# V4.net
KiCad netlist of a schematic drawn in Altium Designer
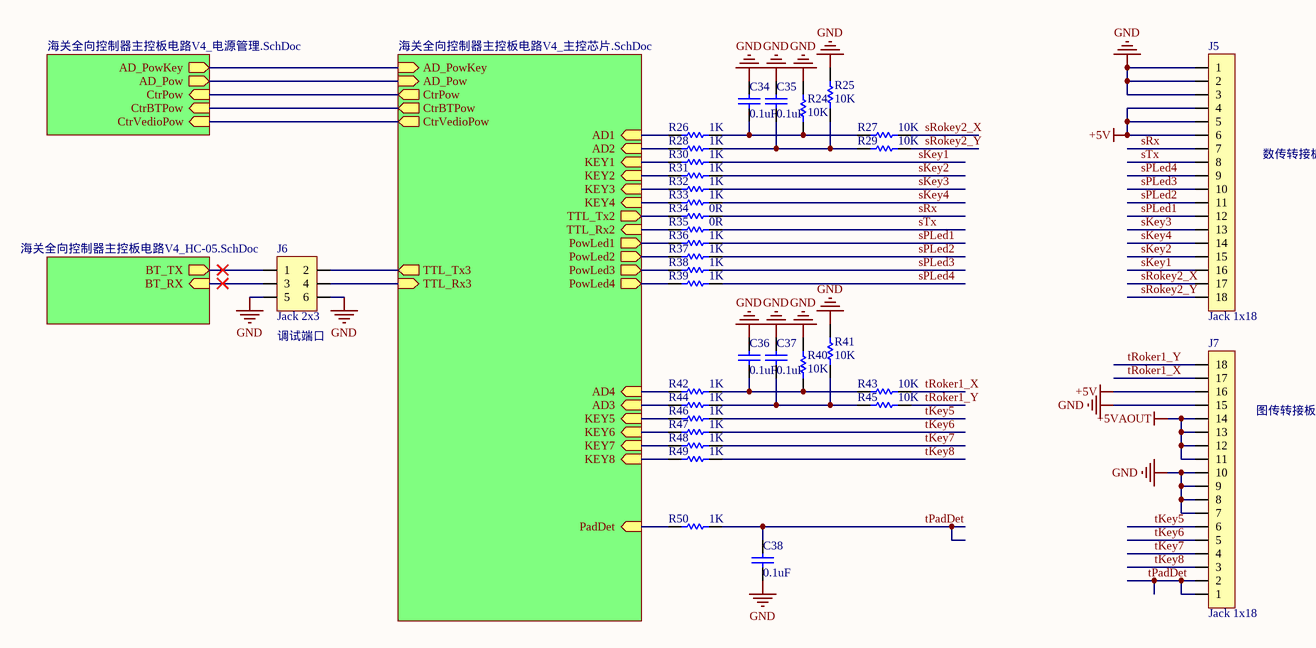
[diagram p0: 海关全向控制器主控板电路V4_系统管理.SchDoc]

(export (version "E")
  (design (tool "Eeschema 10.0.6"))
  (components
    (comp (ref "C34")
      (value "0.1uF")
      (footprint "C0805")
      (description "Capacitor")
      (fields (field (name "PUBLISHER") "Altium Limited"))
      (libsource (lib "RLCYDF") (part "Cap"))
    )
    (comp (ref "C35")
      (value "0.1uF")
      (footprint "C0805")
      (description "Capacitor")
      (fields (field (name "PUBLISHER") "Altium Limited"))
      (libsource (lib "RLCYDF") (part "Cap"))
    )
    (comp (ref "C36")
      (value "0.1uF")
      (footprint "C0805")
      (description "Capacitor")
      (fields (field (name "PUBLISHER") "Altium Limited"))
      (libsource (lib "RLCYDF") (part "Cap"))
    )
    (comp (ref "C37")
      (value "0.1uF")
      (footprint "C0805")
      (description "Capacitor")
      (fields (field (name "PUBLISHER") "Altium Limited"))
      (libsource (lib "RLCYDF") (part "Cap"))
    )
    (comp (ref "C38")
      (value "0.1uF")
      (footprint "C0805")
      (description "Capacitor")
      (fields (field (name "PUBLISHER") "Altium Limited"))
      (libsource (lib "RLCYDF") (part "Cap"))
    )
    (comp (ref "J5")
      (value "Jack 1x18")
      (footprint "0.5S-6X-18PB")
      (description "插座")
      (libsource (lib "") (part "Jack 1x18_1"))
    )
    (comp (ref "J6")
      (value "Jack 2x3")
      (footprint "Jk2*3-2.0")
      (description "双排座")
      (libsource (lib "Connector") (part "Jack 2x3"))
    )
    (comp (ref "J7")
      (value "Jack 1x18")
      (footprint "0.5S-6X-18PB")
      (description "插座")
      (libsource (lib "Connector") (part "Jack 1x18"))
    )
    (comp (ref "R24") (value "10K") (footprint "R0805") (libsource (lib "RLCYDF") (part "Res")))
    (comp (ref "R25") (value "10K") (footprint "R0805") (libsource (lib "RLCYDF") (part "Res")))
    (comp (ref "R26") (value "1K") (footprint "R0805") (libsource (lib "RLCYDF") (part "Res")))
    (comp (ref "R27") (value "10K") (footprint "R0805") (libsource (lib "RLCYDF") (part "Res")))
    (comp (ref "R28") (value "1K") (footprint "R0805") (libsource (lib "RLCYDF") (part "Res")))
    (comp (ref "R29") (value "10K") (footprint "R0805") (libsource (lib "RLCYDF") (part "Res")))
    (comp (ref "R30") (value "1K") (footprint "R0805") (libsource (lib "RLCYDF") (part "Res")))
    (comp (ref "R31") (value "1K") (footprint "R0805") (libsource (lib "RLCYDF") (part "Res")))
    (comp (ref "R32") (value "1K") (footprint "R0805") (libsource (lib "RLCYDF") (part "Res")))
    (comp (ref "R33") (value "1K") (footprint "R0805") (libsource (lib "RLCYDF") (part "Res")))
    (comp (ref "R34") (value "0R") (footprint "R0805") (libsource (lib "RLCYDF") (part "Res")))
    (comp (ref "R35") (value "0R") (footprint "R0805") (libsource (lib "RLCYDF") (part "Res")))
    (comp (ref "R36") (value "1K") (footprint "R0805") (libsource (lib "RLCYDF") (part "Res")))
    (comp (ref "R37") (value "1K") (footprint "R0805") (libsource (lib "RLCYDF") (part "Res")))
    (comp (ref "R38") (value "1K") (footprint "R0805") (libsource (lib "RLCYDF") (part "Res")))
    (comp (ref "R39") (value "1K") (footprint "R0805") (libsource (lib "RLCYDF") (part "Res")))
    (comp (ref "R40") (value "10K") (footprint "R0805") (libsource (lib "RLCYDF") (part "Res")))
    (comp (ref "R41") (value "10K") (footprint "R0805") (libsource (lib "RLCYDF") (part "Res")))
    (comp (ref "R42") (value "1K") (footprint "R0805") (libsource (lib "RLCYDF") (part "Res")))
    (comp (ref "R43") (value "10K") (footprint "R0805") (libsource (lib "RLCYDF") (part "Res")))
    (comp (ref "R44") (value "1K") (footprint "R0805") (libsource (lib "RLCYDF") (part "Res")))
    (comp (ref "R45") (value "10K") (footprint "R0805") (libsource (lib "RLCYDF") (part "Res")))
    (comp (ref "R46") (value "1K") (footprint "R0805") (libsource (lib "RLCYDF") (part "Res")))
    (comp (ref "R47") (value "1K") (footprint "R0805") (libsource (lib "RLCYDF") (part "Res")))
    (comp (ref "R48") (value "1K") (footprint "R0805") (libsource (lib "RLCYDF") (part "Res")))
    (comp (ref "R49") (value "1K") (footprint "R0805") (libsource (lib "RLCYDF") (part "Res")))
    (comp (ref "R50") (value "1K") (footprint "R0805") (libsource (lib "RLCYDF") (part "Res")))
  )
  (nets
    (net (code "1") (name "+5V") (class "Default")
      (node (ref "J5") (pin "4") (pinfunction "4_4") (pintype "passive"))
      (node (ref "J5") (pin "5") (pinfunction "5_5") (pintype "passive"))
      (node (ref "J5") (pin "6") (pinfunction "6_6") (pintype "passive"))
      (node (ref "J7") (pin "16") (pinfunction "16_16") (pintype "passive"))
    )
    (net (code "2") (name "+5VAOUT") (class "Default")
      (node (ref "J7") (pin "11") (pinfunction "11_11") (pintype "passive"))
      (node (ref "J7") (pin "12") (pinfunction "12_12") (pintype "passive"))
      (node (ref "J7") (pin "13") (pinfunction "13_13") (pintype "passive"))
      (node (ref "J7") (pin "14") (pinfunction "14_14") (pintype "passive"))
    )
    (net (code "3") (name "/AD1") (class "Default")
      (node (ref "R26") (pin "2") (pinfunction "2_2") (pintype "passive"))
    )
    (net (code "4") (name "/AD2") (class "Default")
      (node (ref "R28") (pin "2") (pinfunction "2_2") (pintype "passive"))
    )
    (net (code "5") (name "/AD3") (class "Default")
      (node (ref "R44") (pin "2") (pinfunction "2_2") (pintype "passive"))
    )
    (net (code "6") (name "/AD4") (class "Default")
      (node (ref "R42") (pin "2") (pinfunction "2_2") (pintype "passive"))
    )
    (net (code "9") (name "/BT_RX") (class "Default")
      (node (ref "J6") (pin "3") (pinfunction "3_3") (pintype "passive"))
    )
    (net (code "10") (name "/BT_TX") (class "Default")
      (node (ref "J6") (pin "1") (pinfunction "1_1") (pintype "passive"))
    )
    (net (code "14") (name "/KEY1") (class "Default")
      (node (ref "R30") (pin "2") (pinfunction "2_2") (pintype "passive"))
    )
    (net (code "15") (name "/KEY2") (class "Default")
      (node (ref "R31") (pin "2") (pinfunction "2_2") (pintype "passive"))
    )
    (net (code "16") (name "/KEY3") (class "Default")
      (node (ref "R32") (pin "2") (pinfunction "2_2") (pintype "passive"))
    )
    (net (code "17") (name "/KEY4") (class "Default")
      (node (ref "R33") (pin "2") (pinfunction "2_2") (pintype "passive"))
    )
    (net (code "18") (name "/KEY5") (class "Default")
      (node (ref "R46") (pin "2") (pinfunction "2_2") (pintype "passive"))
    )
    (net (code "19") (name "/KEY6") (class "Default")
      (node (ref "R47") (pin "2") (pinfunction "2_2") (pintype "passive"))
    )
    (net (code "20") (name "/KEY7") (class "Default")
      (node (ref "R48") (pin "2") (pinfunction "2_2") (pintype "passive"))
    )
    (net (code "21") (name "/KEY8") (class "Default")
      (node (ref "R49") (pin "2") (pinfunction "2_2") (pintype "passive"))
    )
    (net (code "22") (name "/PadDet") (class "Default")
      (node (ref "R50") (pin "2") (pinfunction "2_2") (pintype "passive"))
    )
    (net (code "23") (name "/PowLed1") (class "Default")
      (node (ref "R36") (pin "2") (pinfunction "2_2") (pintype "passive"))
    )
    (net (code "24") (name "/PowLed2") (class "Default")
      (node (ref "R37") (pin "2") (pinfunction "2_2") (pintype "passive"))
    )
    (net (code "25") (name "/PowLed3") (class "Default")
      (node (ref "R38") (pin "2") (pinfunction "2_2") (pintype "passive"))
    )
    (net (code "26") (name "/PowLed4") (class "Default")
      (node (ref "R39") (pin "2") (pinfunction "2_2") (pintype "passive"))
    )
    (net (code "27") (name "/TTL_Rx2") (class "Default")
      (node (ref "R35") (pin "2") (pinfunction "2_2") (pintype "passive"))
    )
    (net (code "28") (name "/TTL_Rx3") (class "Default")
      (node (ref "J6") (pin "4") (pinfunction "4_4") (pintype "passive"))
    )
    (net (code "29") (name "/TTL_Tx2") (class "Default")
      (node (ref "R34") (pin "2") (pinfunction "2_2") (pintype "passive"))
    )
    (net (code "30") (name "/TTL_Tx3") (class "Default")
      (node (ref "J6") (pin "2") (pinfunction "2_2") (pintype "passive"))
    )
    (net (code "31") (name "/sKey1") (class "Default")
      (node (ref "J5") (pin "16") (pinfunction "16_16") (pintype "passive"))
      (node (ref "R30") (pin "1") (pinfunction "1_1") (pintype "passive"))
    )
    (net (code "32") (name "/sKey2") (class "Default")
      (node (ref "J5") (pin "15") (pinfunction "15_15") (pintype "passive"))
      (node (ref "R31") (pin "1") (pinfunction "1_1") (pintype "passive"))
    )
    (net (code "33") (name "/sKey3") (class "Default")
      (node (ref "J5") (pin "13") (pinfunction "13_13") (pintype "passive"))
      (node (ref "R32") (pin "1") (pinfunction "1_1") (pintype "passive"))
    )
    (net (code "34") (name "/sKey4") (class "Default")
      (node (ref "J5") (pin "14") (pinfunction "14_14") (pintype "passive"))
      (node (ref "R33") (pin "1") (pinfunction "1_1") (pintype "passive"))
    )
    (net (code "35") (name "/sPLed1") (class "Default")
      (node (ref "J5") (pin "12") (pinfunction "12_12") (pintype "passive"))
      (node (ref "R36") (pin "1") (pinfunction "1_1") (pintype "passive"))
    )
    (net (code "36") (name "/sPLed2") (class "Default")
      (node (ref "J5") (pin "11") (pinfunction "11_11") (pintype "passive"))
      (node (ref "R37") (pin "1") (pinfunction "1_1") (pintype "passive"))
    )
    (net (code "37") (name "/sPLed3") (class "Default")
      (node (ref "J5") (pin "10") (pinfunction "10_10") (pintype "passive"))
      (node (ref "R38") (pin "1") (pinfunction "1_1") (pintype "passive"))
    )
    (net (code "38") (name "/sPLed4") (class "Default")
      (node (ref "J5") (pin "9") (pinfunction "9_9") (pintype "passive"))
      (node (ref "R39") (pin "1") (pinfunction "1_1") (pintype "passive"))
    )
    (net (code "39") (name "/sRokey2_X") (class "Default")
      (node (ref "J5") (pin "17") (pinfunction "17_17") (pintype "passive"))
      (node (ref "R27") (pin "1") (pinfunction "1_1") (pintype "passive"))
    )
    (net (code "40") (name "/sRokey2_Y") (class "Default")
      (node (ref "J5") (pin "18") (pinfunction "18_18") (pintype "passive"))
      (node (ref "R29") (pin "1") (pinfunction "1_1") (pintype "passive"))
    )
    (net (code "41") (name "/sRx") (class "Default")
      (node (ref "J5") (pin "7") (pinfunction "7_7") (pintype "passive"))
      (node (ref "R34") (pin "1") (pinfunction "1_1") (pintype "passive"))
    )
    (net (code "42") (name "/sTx") (class "Default")
      (node (ref "J5") (pin "8") (pinfunction "8_8") (pintype "passive"))
      (node (ref "R35") (pin "1") (pinfunction "1_1") (pintype "passive"))
    )
    (net (code "43") (name "/tKey5") (class "Default")
      (node (ref "J7") (pin "6") (pinfunction "6_6") (pintype "passive"))
      (node (ref "R46") (pin "1") (pinfunction "1_1") (pintype "passive"))
    )
    (net (code "44") (name "/tKey6") (class "Default")
      (node (ref "J7") (pin "5") (pinfunction "5_5") (pintype "passive"))
      (node (ref "R47") (pin "1") (pinfunction "1_1") (pintype "passive"))
    )
    (net (code "45") (name "/tKey7") (class "Default")
      (node (ref "J7") (pin "4") (pinfunction "4_4") (pintype "passive"))
      (node (ref "R48") (pin "1") (pinfunction "1_1") (pintype "passive"))
    )
    (net (code "46") (name "/tKey8") (class "Default")
      (node (ref "J7") (pin "3") (pinfunction "3_3") (pintype "passive"))
      (node (ref "R49") (pin "1") (pinfunction "1_1") (pintype "passive"))
    )
    (net (code "47") (name "/tPadDet") (class "Default")
      (node (ref "C38") (pin "2") (pinfunction "2_2") (pintype "passive"))
      (node (ref "J7") (pin "1") (pinfunction "1_1") (pintype "passive"))
      (node (ref "J7") (pin "2") (pinfunction "2_2") (pintype "passive"))
      (node (ref "R50") (pin "1") (pinfunction "1_1") (pintype "passive"))
    )
    (net (code "48") (name "/tRoker1_X") (class "Default")
      (node (ref "J7") (pin "17") (pinfunction "17_17") (pintype "passive"))
      (node (ref "R43") (pin "1") (pinfunction "1_1") (pintype "passive"))
    )
    (net (code "49") (name "/tRoker1_Y") (class "Default")
      (node (ref "J7") (pin "18") (pinfunction "18_18") (pintype "passive"))
      (node (ref "R45") (pin "1") (pinfunction "1_1") (pintype "passive"))
    )
    (net (code "50") (name "GND") (class "Default")
      (node (ref "C34") (pin "2") (pinfunction "2_2") (pintype "passive"))
      (node (ref "C35") (pin "2") (pinfunction "2_2") (pintype "passive"))
      (node (ref "C36") (pin "2") (pinfunction "2_2") (pintype "passive"))
      (node (ref "C37") (pin "2") (pinfunction "2_2") (pintype "passive"))
      (node (ref "C38") (pin "1") (pinfunction "1_1") (pintype "passive"))
      (node (ref "J5") (pin "1") (pinfunction "1_1") (pintype "passive"))
      (node (ref "J5") (pin "2") (pinfunction "2_2") (pintype "passive"))
      (node (ref "J5") (pin "3") (pinfunction "3_3") (pintype "passive"))
      (node (ref "J6") (pin "5") (pinfunction "5_5") (pintype "passive"))
      (node (ref "J6") (pin "6") (pinfunction "6_6") (pintype "passive"))
      (node (ref "J7") (pin "10") (pinfunction "10_10") (pintype "passive"))
      (node (ref "J7") (pin "15") (pinfunction "15_15") (pintype "passive"))
      (node (ref "J7") (pin "7") (pinfunction "7_7") (pintype "passive"))
      (node (ref "J7") (pin "8") (pinfunction "8_8") (pintype "passive"))
      (node (ref "J7") (pin "9") (pinfunction "9_9") (pintype "passive"))
      (node (ref "R24") (pin "1") (pinfunction "1_1") (pintype "passive"))
      (node (ref "R25") (pin "1") (pinfunction "1_1") (pintype "passive"))
      (node (ref "R40") (pin "1") (pinfunction "1_1") (pintype "passive"))
      (node (ref "R41") (pin "1") (pinfunction "1_1") (pintype "passive"))
    )
    (net (code "51") (name "Net-(C34-Pad1)") (class "Default")
      (node (ref "C34") (pin "1") (pinfunction "1_1") (pintype "passive"))
      (node (ref "R24") (pin "2") (pinfunction "2_2") (pintype "passive"))
      (node (ref "R26") (pin "1") (pinfunction "1_1") (pintype "passive"))
      (node (ref "R27") (pin "2") (pinfunction "2_2") (pintype "passive"))
    )
    (net (code "52") (name "Net-(C35-Pad1)") (class "Default")
      (node (ref "C35") (pin "1") (pinfunction "1_1") (pintype "passive"))
      (node (ref "R25") (pin "2") (pinfunction "2_2") (pintype "passive"))
      (node (ref "R28") (pin "1") (pinfunction "1_1") (pintype "passive"))
      (node (ref "R29") (pin "2") (pinfunction "2_2") (pintype "passive"))
    )
    (net (code "53") (name "Net-(C36-Pad1)") (class "Default")
      (node (ref "C36") (pin "1") (pinfunction "1_1") (pintype "passive"))
      (node (ref "R40") (pin "2") (pinfunction "2_2") (pintype "passive"))
      (node (ref "R42") (pin "1") (pinfunction "1_1") (pintype "passive"))
      (node (ref "R43") (pin "2") (pinfunction "2_2") (pintype "passive"))
    )
    (net (code "54") (name "Net-(C37-Pad1)") (class "Default")
      (node (ref "C37") (pin "1") (pinfunction "1_1") (pintype "passive"))
      (node (ref "R41") (pin "2") (pinfunction "2_2") (pintype "passive"))
      (node (ref "R44") (pin "1") (pinfunction "1_1") (pintype "passive"))
      (node (ref "R45") (pin "2") (pinfunction "2_2") (pintype "passive"))
    )
  )
)
